# ProPrj_terminal-bus_2024-09-02.net
KiCad netlist of a schematic drawn in EasyEDA Pro
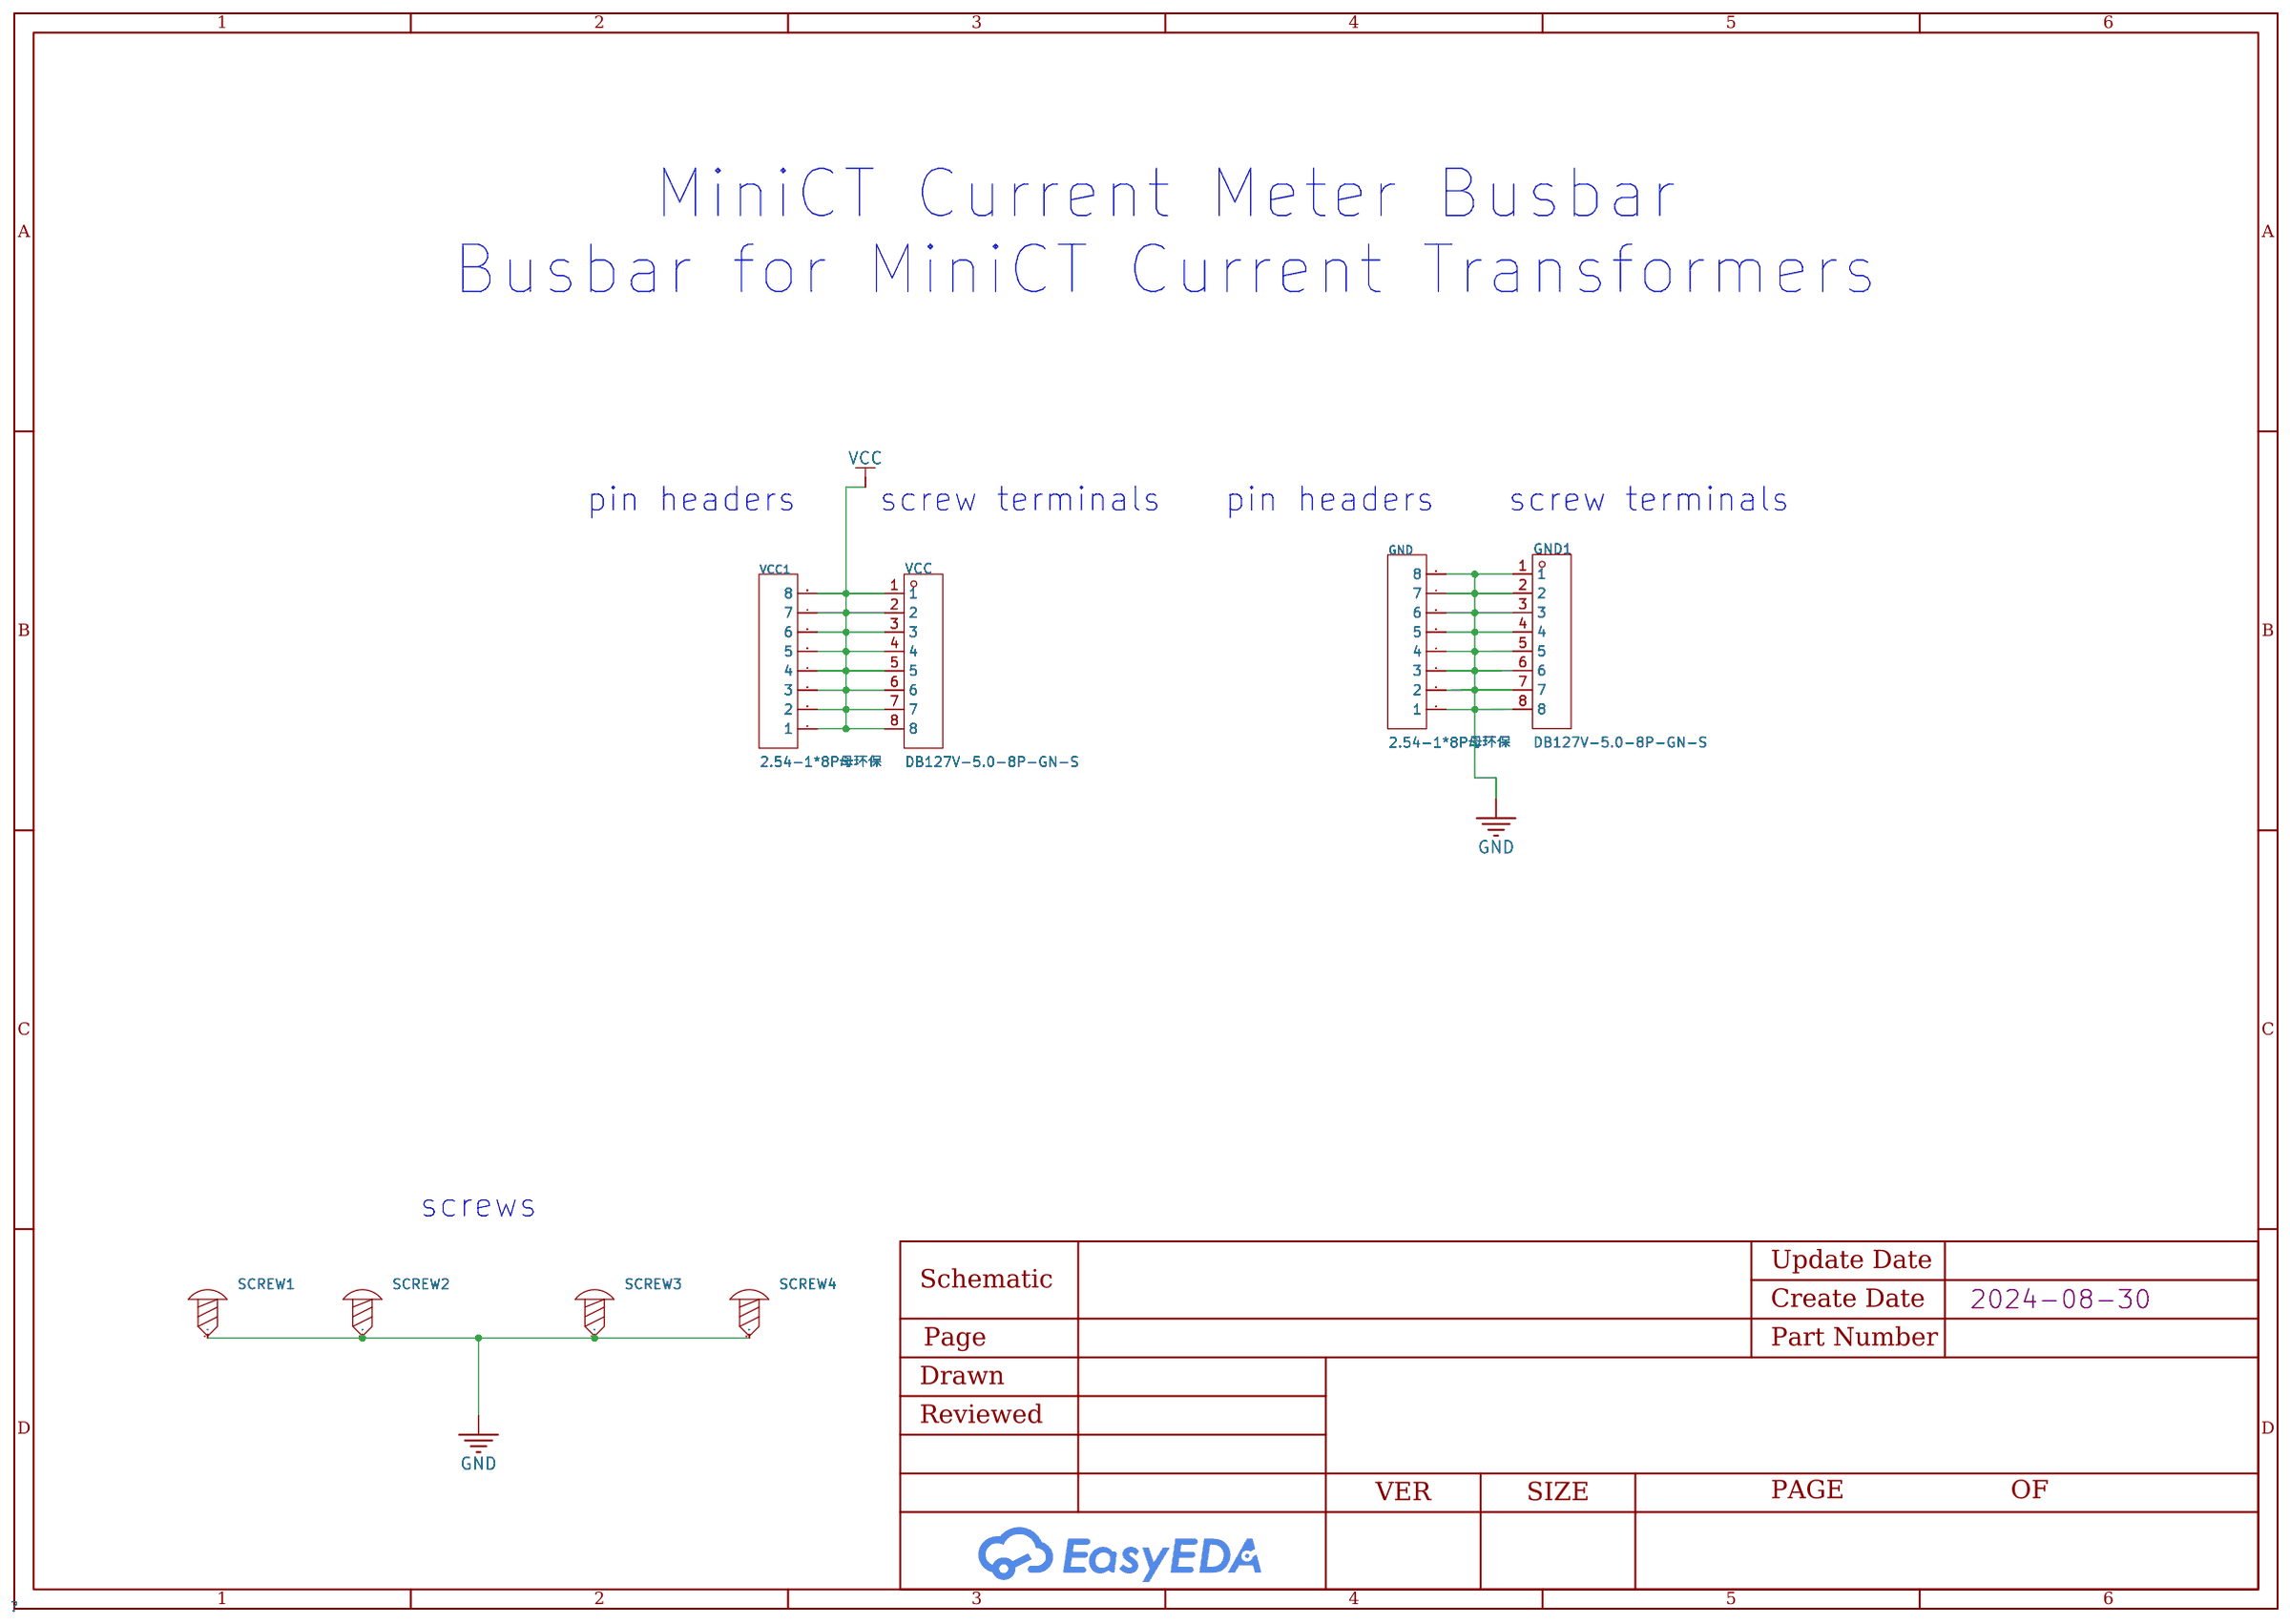
[diagram p0: schematic sheet]

(export (version "E")
  (design (tool "Eeschema 10.0.6"))
  (components
    (comp (ref "GND")
      (value "2.54-1*8P母环保")
      (footprint "easyedapro:HDR-TH_8P-P2.54-V-F-1")
      (fields (field (name "Manufacturer") "BOOMELE(博穆精密)"))
      (libsource (lib "easyedapro") (part "Header-Female-2.54_1x8"))
    )
    (comp (ref "GND1")
      (value "DB127V-5.0-8P-GN-S")
      (footprint "easyedapro:CONN-TH_8P-P5.00_DB127V-5.0-8P-GN-S")
      (fields (field (name "Manufacturer") "DORABO(地博电气)"))
      (libsource (lib "easyedapro") (part "DB127V-5.0-8P-GN-S"))
    )
    (comp (ref "SCREW1")
      (value "~")
      (footprint "easyedapro:Screw-Hole-M2")
      (libsource (lib "easyedapro") (part "Screw-Hole"))
    )
    (comp (ref "SCREW2")
      (value "~")
      (footprint "easyedapro:Screw-Hole-M2")
      (libsource (lib "easyedapro") (part "Screw-Hole"))
    )
    (comp (ref "SCREW3")
      (value "~")
      (footprint "easyedapro:Screw-Hole-M2")
      (libsource (lib "easyedapro") (part "Screw-Hole"))
    )
    (comp (ref "SCREW4")
      (value "~")
      (footprint "easyedapro:Screw-Hole-M2")
      (libsource (lib "easyedapro") (part "Screw-Hole"))
    )
    (comp (ref "VCC")
      (value "DB127V-5.0-8P-GN-S")
      (footprint "easyedapro:CONN-TH_8P-P5.00_DB127V-5.0-8P-GN-S")
      (fields (field (name "Manufacturer") "DORABO(地博电气)"))
      (libsource (lib "easyedapro") (part "DB127V-5.0-8P-GN-S"))
    )
    (comp (ref "VCC1")
      (value "2.54-1*8P母环保")
      (footprint "easyedapro:HDR-TH_8P-P2.54-V-F-1")
      (fields (field (name "Manufacturer") "BOOMELE(博穆精密)"))
      (libsource (lib "easyedapro") (part "Header-Female-2.54_1x8"))
    )
  )
  (nets
    (net (code "1") (name "GND") (class "Default")
      (node (ref "GND") (pin "1") (pinfunction "1_1") (pintype "input"))
      (node (ref "GND") (pin "2") (pinfunction "2_2") (pintype "input"))
      (node (ref "GND") (pin "3") (pinfunction "3_3") (pintype "input"))
      (node (ref "GND") (pin "4") (pinfunction "4_4") (pintype "input"))
      (node (ref "GND") (pin "5") (pinfunction "5_5") (pintype "input"))
      (node (ref "GND") (pin "6") (pinfunction "6_6") (pintype "input"))
      (node (ref "GND") (pin "7") (pinfunction "7_7") (pintype "input"))
      (node (ref "GND") (pin "8") (pinfunction "8_8") (pintype "input"))
      (node (ref "GND1") (pin "5") (pinfunction "5_5") (pintype "unspecified"))
      (node (ref "GND1") (pin "6") (pinfunction "6_6") (pintype "unspecified"))
      (node (ref "GND1") (pin "7") (pinfunction "7_7") (pintype "unspecified"))
      (node (ref "GND1") (pin "8") (pinfunction "8_8") (pintype "unspecified"))
      (node (ref "SCREW1") (pin "1") (pinfunction "1_1") (pintype "input"))
      (node (ref "SCREW2") (pin "1") (pinfunction "1_1") (pintype "input"))
      (node (ref "SCREW3") (pin "1") (pinfunction "1_1") (pintype "input"))
      (node (ref "SCREW4") (pin "1") (pinfunction "1_1") (pintype "input"))
    )
    (net (code "2") (name "VCC") (class "Default")
      (node (ref "VCC") (pin "1") (pinfunction "1_1") (pintype "unspecified"))
      (node (ref "VCC") (pin "2") (pinfunction "2_2") (pintype "unspecified"))
      (node (ref "VCC") (pin "3") (pinfunction "3_3") (pintype "unspecified"))
      (node (ref "VCC") (pin "4") (pinfunction "4_4") (pintype "unspecified"))
      (node (ref "VCC") (pin "5") (pinfunction "5_5") (pintype "unspecified"))
      (node (ref "VCC") (pin "6") (pinfunction "6_6") (pintype "unspecified"))
      (node (ref "VCC") (pin "7") (pinfunction "7_7") (pintype "unspecified"))
      (node (ref "VCC") (pin "8") (pinfunction "8_8") (pintype "unspecified"))
      (node (ref "VCC1") (pin "1") (pinfunction "1_1") (pintype "input"))
      (node (ref "VCC1") (pin "2") (pinfunction "2_2") (pintype "input"))
      (node (ref "VCC1") (pin "3") (pinfunction "3_3") (pintype "input"))
      (node (ref "VCC1") (pin "4") (pinfunction "4_4") (pintype "input"))
      (node (ref "VCC1") (pin "5") (pinfunction "5_5") (pintype "input"))
      (node (ref "VCC1") (pin "6") (pinfunction "6_6") (pintype "input"))
      (node (ref "VCC1") (pin "7") (pinfunction "7_7") (pintype "input"))
      (node (ref "VCC1") (pin "8") (pinfunction "8_8") (pintype "input"))
    )
    (net (code "3") (name "unconnected-(GND1-Pad1)") (class "Default")
      (node (ref "GND1") (pin "1") (pinfunction "1_1") (pintype "unspecified"))
    )
    (net (code "4") (name "unconnected-(GND1-Pad2)") (class "Default")
      (node (ref "GND1") (pin "2") (pinfunction "2_2") (pintype "unspecified"))
    )
    (net (code "5") (name "unconnected-(GND1-Pad3)") (class "Default")
      (node (ref "GND1") (pin "3") (pinfunction "3_3") (pintype "unspecified"))
    )
    (net (code "6") (name "unconnected-(GND1-Pad4)") (class "Default")
      (node (ref "GND1") (pin "4") (pinfunction "4_4") (pintype "unspecified"))
    )
  )
)
